# pcf8591-board.net
KiCad netlist of a schematic drawn in EAGLE
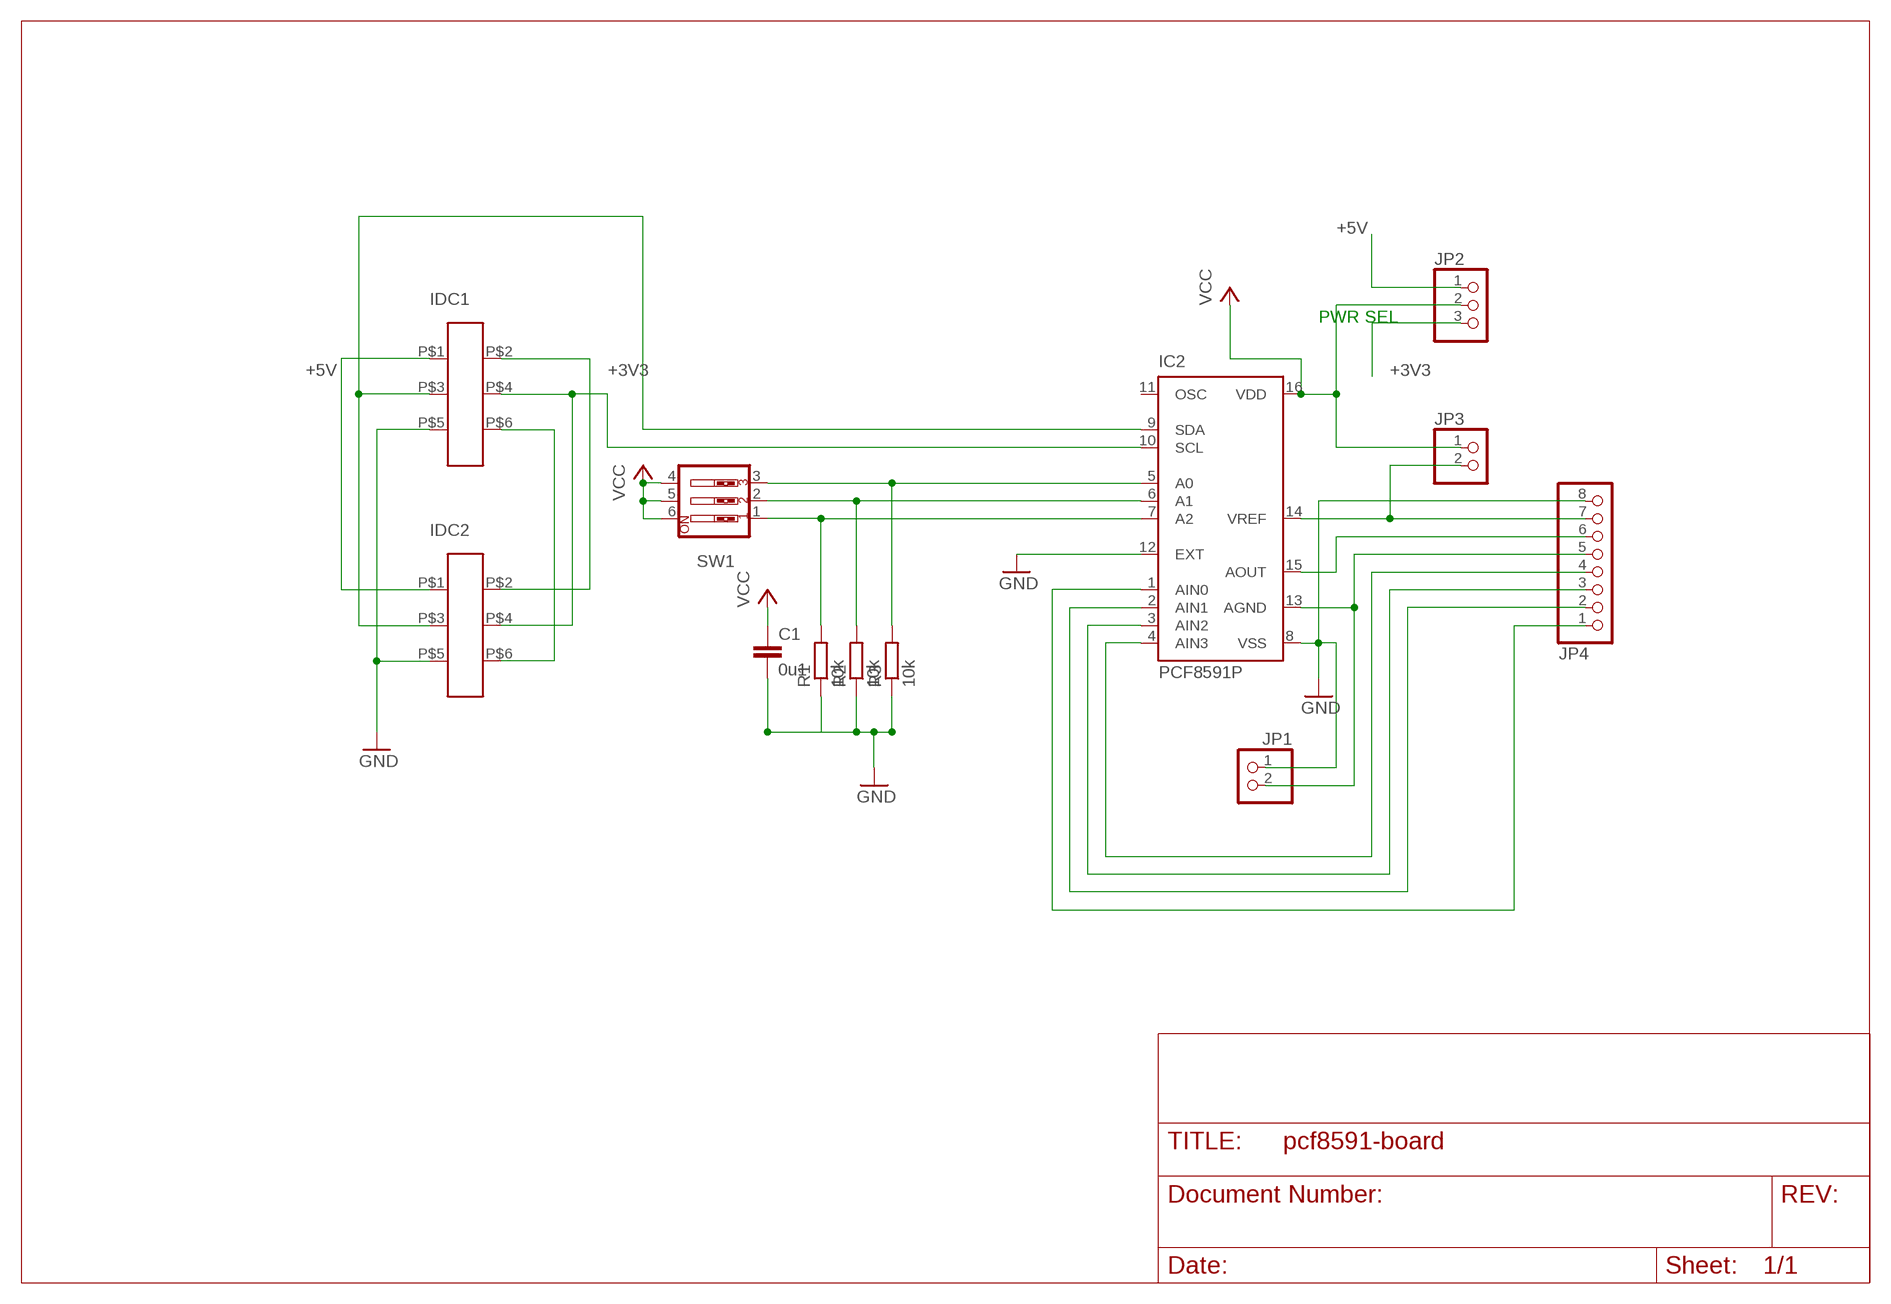
[diagram p0: schematic, sheet 1]

(export (version "E")
  (design (tool "Eeschema 10.0.6"))
  (components
    (comp (ref "C1")
      (value "0u1")
      (footprint "eagle-import:C025-030X050")
      (libsource (lib "eagle-import") (part "C-EU025-030X050"))
    )
    (comp (ref "IC2")
      (value "PCF8591P")
      (footprint "eagle-import:DIL16")
      (fields (field (name "MF") "FARNELL"))
      (libsource (lib "eagle-import") (part "PCF8591P"))
    )
    (comp (ref "IDC1")
      (value "IDC-6W")
      (footprint "eagle-import:IDC-6W")
      (libsource (lib "eagle-import") (part "IDC-6W"))
    )
    (comp (ref "IDC2")
      (value "IDC-6W")
      (footprint "eagle-import:IDC-6W")
      (libsource (lib "eagle-import") (part "IDC-6W"))
    )
    (comp (ref "JP1")
      (value "PINHD-1X2")
      (footprint "eagle-import:1X02")
      (libsource (lib "eagle-import") (part "PINHD-1X2"))
    )
    (comp (ref "JP2")
      (value "PINHD-1X3")
      (footprint "eagle-import:1X03")
      (libsource (lib "eagle-import") (part "PINHD-1X3"))
    )
    (comp (ref "JP3")
      (value "PINHD-1X2")
      (footprint "eagle-import:1X02")
      (libsource (lib "eagle-import") (part "PINHD-1X2"))
    )
    (comp (ref "JP4")
      (value "PINHD-1X8")
      (footprint "eagle-import:1X08")
      (libsource (lib "eagle-import") (part "PINHD-1X8"))
    )
    (comp (ref "R1")
      (value "10k")
      (footprint "eagle-import:0204_7")
      (libsource (lib "eagle-import") (part "R-EU_0204/7"))
    )
    (comp (ref "R2")
      (value "10k")
      (footprint "eagle-import:0204_7")
      (libsource (lib "eagle-import") (part "R-EU_0204/7"))
    )
    (comp (ref "R3")
      (value "10k")
      (footprint "eagle-import:0204_7")
      (libsource (lib "eagle-import") (part "R-EU_0204/7"))
    )
    (comp (ref "SW1")
      (value "SW_DIP-3")
      (footprint "eagle-import:EDG-03")
      (libsource (lib "eagle-import") (part "SW_DIP-3"))
    )
  )
  (nets
    (net (code "1") (name "/+3V3") (class "Default")
      (node (ref "IDC1") (pin "P$2") (pinfunction "P$2_P$2") (pintype "bidirectional"))
      (node (ref "IDC2") (pin "P$2") (pinfunction "P$2_P$2") (pintype "bidirectional"))
      (node (ref "JP2") (pin "3") (pinfunction "3_3") (pintype "passive"))
    )
    (net (code "2") (name "/+5V") (class "Default")
      (node (ref "IDC1") (pin "P$1") (pinfunction "P$1_P$1") (pintype "bidirectional"))
      (node (ref "IDC2") (pin "P$1") (pinfunction "P$1_P$1") (pintype "bidirectional"))
      (node (ref "JP2") (pin "1") (pinfunction "1_1") (pintype "passive"))
    )
    (net (code "3") (name "GND") (class "Default")
      (node (ref "C1") (pin "2") (pinfunction "2_2") (pintype "passive"))
      (node (ref "IC2") (pin "12") (pinfunction "EXT_12") (pintype "input"))
      (node (ref "IC2") (pin "8") (pinfunction "VSS_8") (pintype "power_in"))
      (node (ref "IDC1") (pin "P$5") (pinfunction "P$5_P$5") (pintype "bidirectional"))
      (node (ref "IDC2") (pin "P$5") (pinfunction "P$5_P$5") (pintype "bidirectional"))
      (node (ref "JP1") (pin "1") (pinfunction "1_1") (pintype "passive"))
      (node (ref "JP4") (pin "8") (pinfunction "8_8") (pintype "passive"))
      (node (ref "R1") (pin "1") (pinfunction "1_1") (pintype "passive"))
      (node (ref "R2") (pin "1") (pinfunction "1_1") (pintype "passive"))
      (node (ref "R3") (pin "1") (pinfunction "1_1") (pintype "passive"))
    )
    (net (code "4") (name "Net-(IC2-A0)") (class "Default")
      (node (ref "IC2") (pin "5") (pinfunction "A0_5") (pintype "input"))
      (node (ref "R3") (pin "2") (pinfunction "2_2") (pintype "passive"))
      (node (ref "SW1") (pin "3") (pinfunction "3_3") (pintype "passive"))
    )
    (net (code "5") (name "Net-(IC2-A1)") (class "Default")
      (node (ref "IC2") (pin "6") (pinfunction "A1_6") (pintype "input"))
      (node (ref "R2") (pin "2") (pinfunction "2_2") (pintype "passive"))
      (node (ref "SW1") (pin "2") (pinfunction "2_2") (pintype "passive"))
    )
    (net (code "6") (name "Net-(IC2-A2)") (class "Default")
      (node (ref "IC2") (pin "7") (pinfunction "A2_7") (pintype "input"))
      (node (ref "R1") (pin "2") (pinfunction "2_2") (pintype "passive"))
      (node (ref "SW1") (pin "1") (pinfunction "1_1") (pintype "passive"))
    )
    (net (code "7") (name "Net-(IC2-AGND)") (class "Default")
      (node (ref "IC2") (pin "13") (pinfunction "AGND_13") (pintype "power_in"))
      (node (ref "JP1") (pin "2") (pinfunction "2_2") (pintype "passive"))
      (node (ref "JP4") (pin "5") (pinfunction "5_5") (pintype "passive"))
    )
    (net (code "8") (name "Net-(IC2-AIN0)") (class "Default")
      (node (ref "IC2") (pin "1") (pinfunction "AIN0_1") (pintype "input"))
      (node (ref "JP4") (pin "1") (pinfunction "1_1") (pintype "passive"))
    )
    (net (code "9") (name "Net-(IC2-AIN1)") (class "Default")
      (node (ref "IC2") (pin "2") (pinfunction "AIN1_2") (pintype "input"))
      (node (ref "JP4") (pin "2") (pinfunction "2_2") (pintype "passive"))
    )
    (net (code "10") (name "Net-(IC2-AIN2)") (class "Default")
      (node (ref "IC2") (pin "3") (pinfunction "AIN2_3") (pintype "input"))
      (node (ref "JP4") (pin "3") (pinfunction "3_3") (pintype "passive"))
    )
    (net (code "11") (name "Net-(IC2-AIN3)") (class "Default")
      (node (ref "IC2") (pin "4") (pinfunction "AIN3_4") (pintype "input"))
      (node (ref "JP4") (pin "4") (pinfunction "4_4") (pintype "passive"))
    )
    (net (code "12") (name "Net-(IC2-AOUT)") (class "Default")
      (node (ref "IC2") (pin "15") (pinfunction "AOUT_15") (pintype "output"))
      (node (ref "JP4") (pin "6") (pinfunction "6_6") (pintype "passive"))
    )
    (net (code "13") (name "Net-(IC2-SCL)") (class "Default")
      (node (ref "IC2") (pin "10") (pinfunction "SCL_10") (pintype "input"))
      (node (ref "IDC1") (pin "P$4") (pinfunction "P$4_P$4") (pintype "bidirectional"))
      (node (ref "IDC2") (pin "P$4") (pinfunction "P$4_P$4") (pintype "bidirectional"))
    )
    (net (code "14") (name "Net-(IC2-SDA)") (class "Default")
      (node (ref "IC2") (pin "9") (pinfunction "SDA_9") (pintype "bidirectional"))
      (node (ref "IDC1") (pin "P$3") (pinfunction "P$3_P$3") (pintype "bidirectional"))
      (node (ref "IDC2") (pin "P$3") (pinfunction "P$3_P$3") (pintype "bidirectional"))
    )
    (net (code "15") (name "Net-(IC2-VREF)") (class "Default")
      (node (ref "IC2") (pin "14") (pinfunction "VREF_14") (pintype "input"))
      (node (ref "JP3") (pin "2") (pinfunction "2_2") (pintype "passive"))
      (node (ref "JP4") (pin "7") (pinfunction "7_7") (pintype "passive"))
    )
    (net (code "16") (name "Net-(IDC1-PadP$6)") (class "Default")
      (node (ref "IDC1") (pin "P$6") (pinfunction "P$6_P$6") (pintype "bidirectional"))
      (node (ref "IDC2") (pin "P$6") (pinfunction "P$6_P$6") (pintype "bidirectional"))
    )
    (net (code "17") (name "VCC") (class "Default")
      (node (ref "C1") (pin "1") (pinfunction "1_1") (pintype "passive"))
      (node (ref "IC2") (pin "16") (pinfunction "VDD_16") (pintype "power_in"))
      (node (ref "JP2") (pin "2") (pinfunction "2_2") (pintype "passive"))
      (node (ref "JP3") (pin "1") (pinfunction "1_1") (pintype "passive"))
      (node (ref "SW1") (pin "4") (pinfunction "4_4") (pintype "passive"))
      (node (ref "SW1") (pin "5") (pinfunction "5_5") (pintype "passive"))
      (node (ref "SW1") (pin "6") (pinfunction "6_6") (pintype "passive"))
    )
    (net (code "18") (name "unconnected-(IC2-OSC-Pad11)") (class "Default")
      (node (ref "IC2") (pin "11") (pinfunction "OSC_11") (pintype "input"))
    )
  )
)
